# yarns_v03.net
KiCad netlist of a schematic drawn in EAGLE
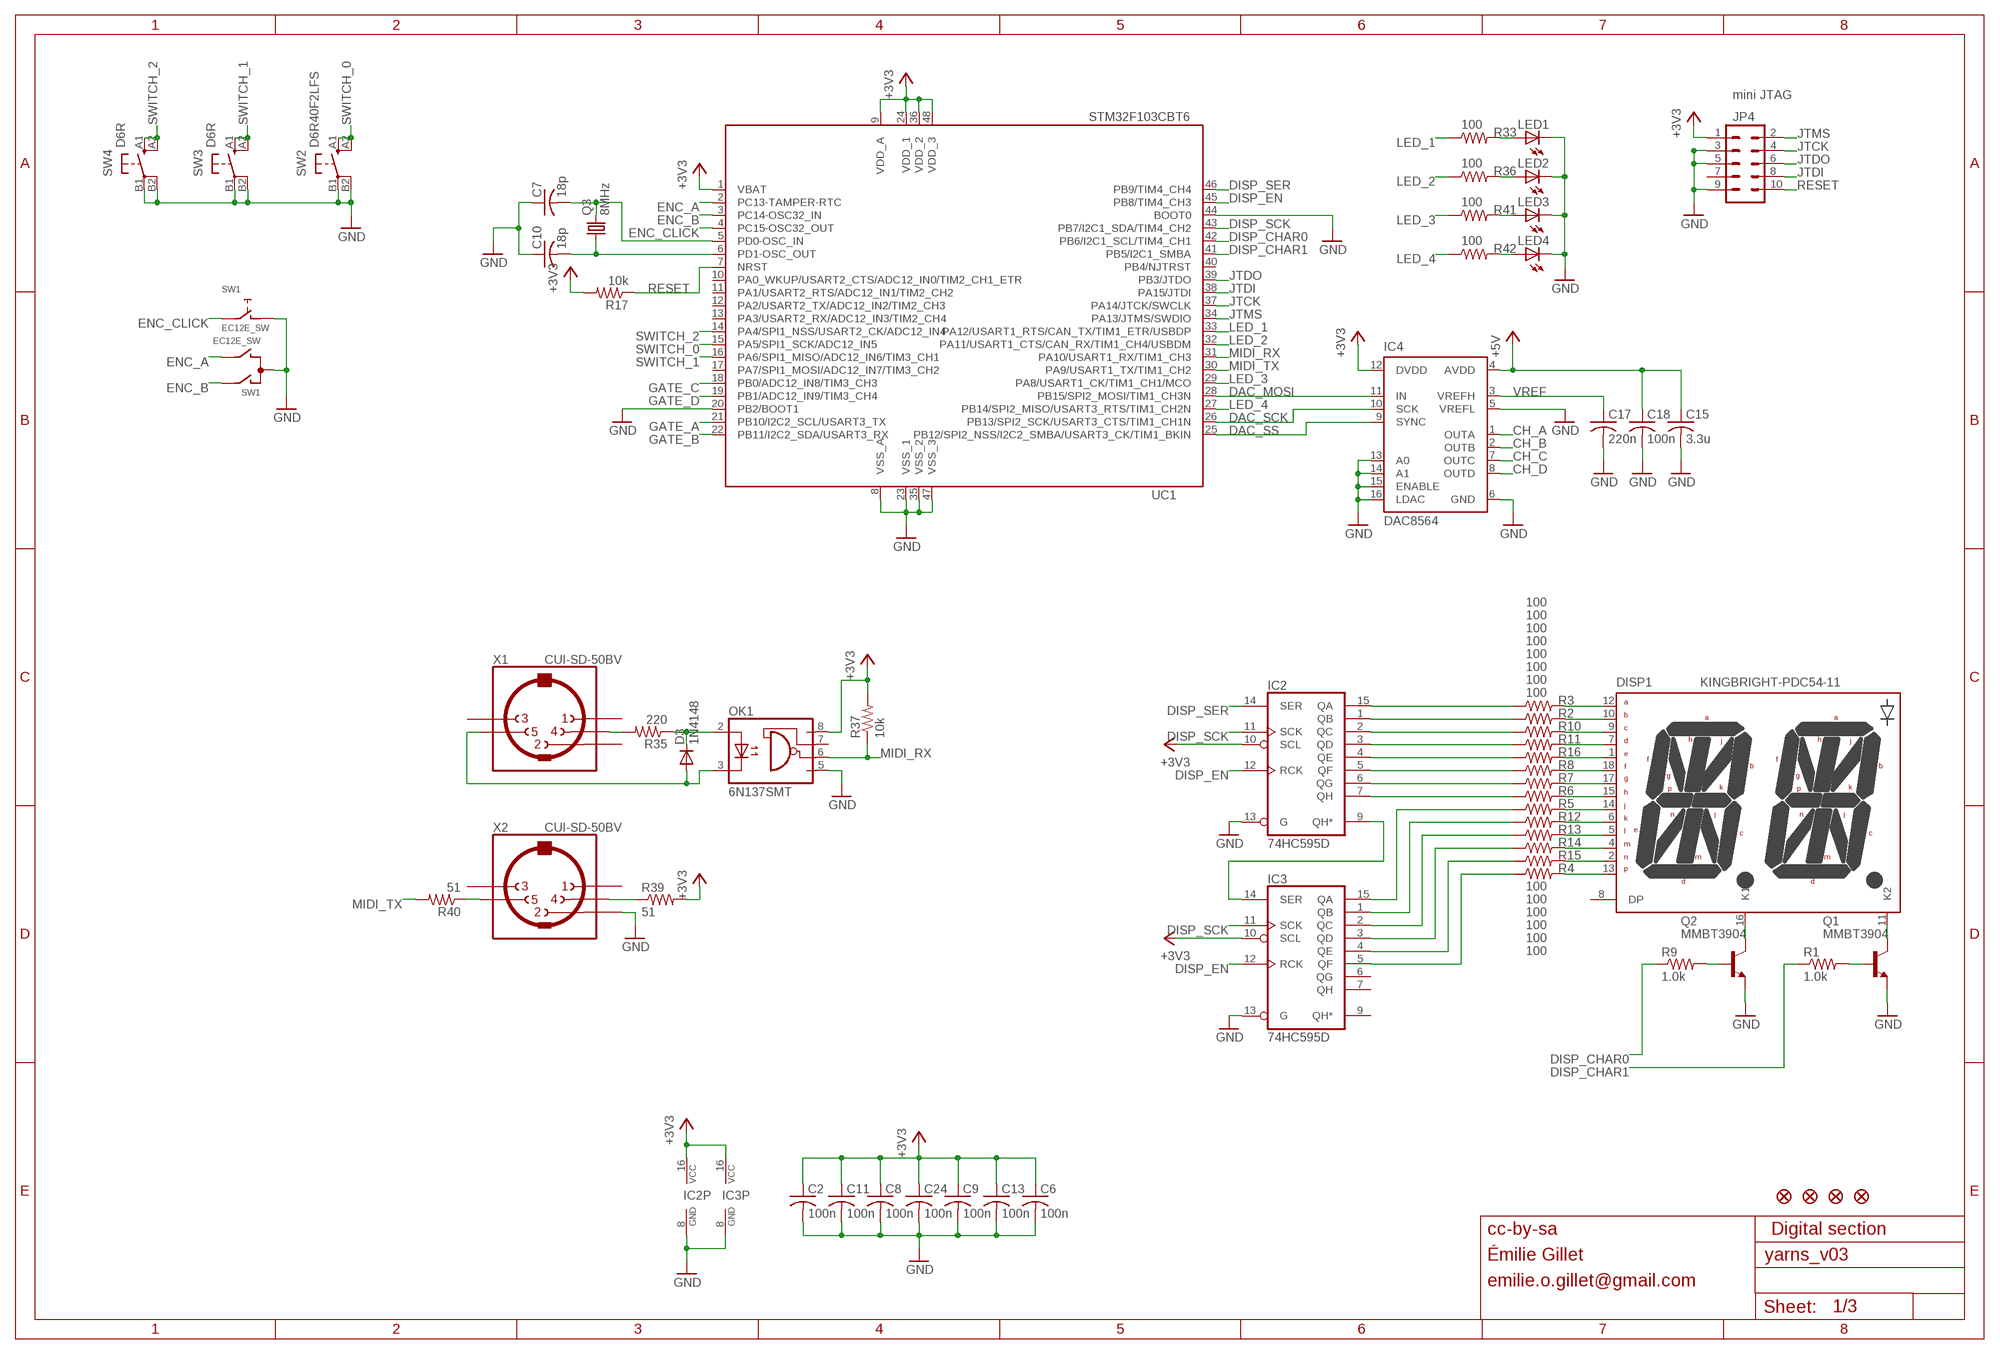
[diagram p0: schematic, sheet 1]
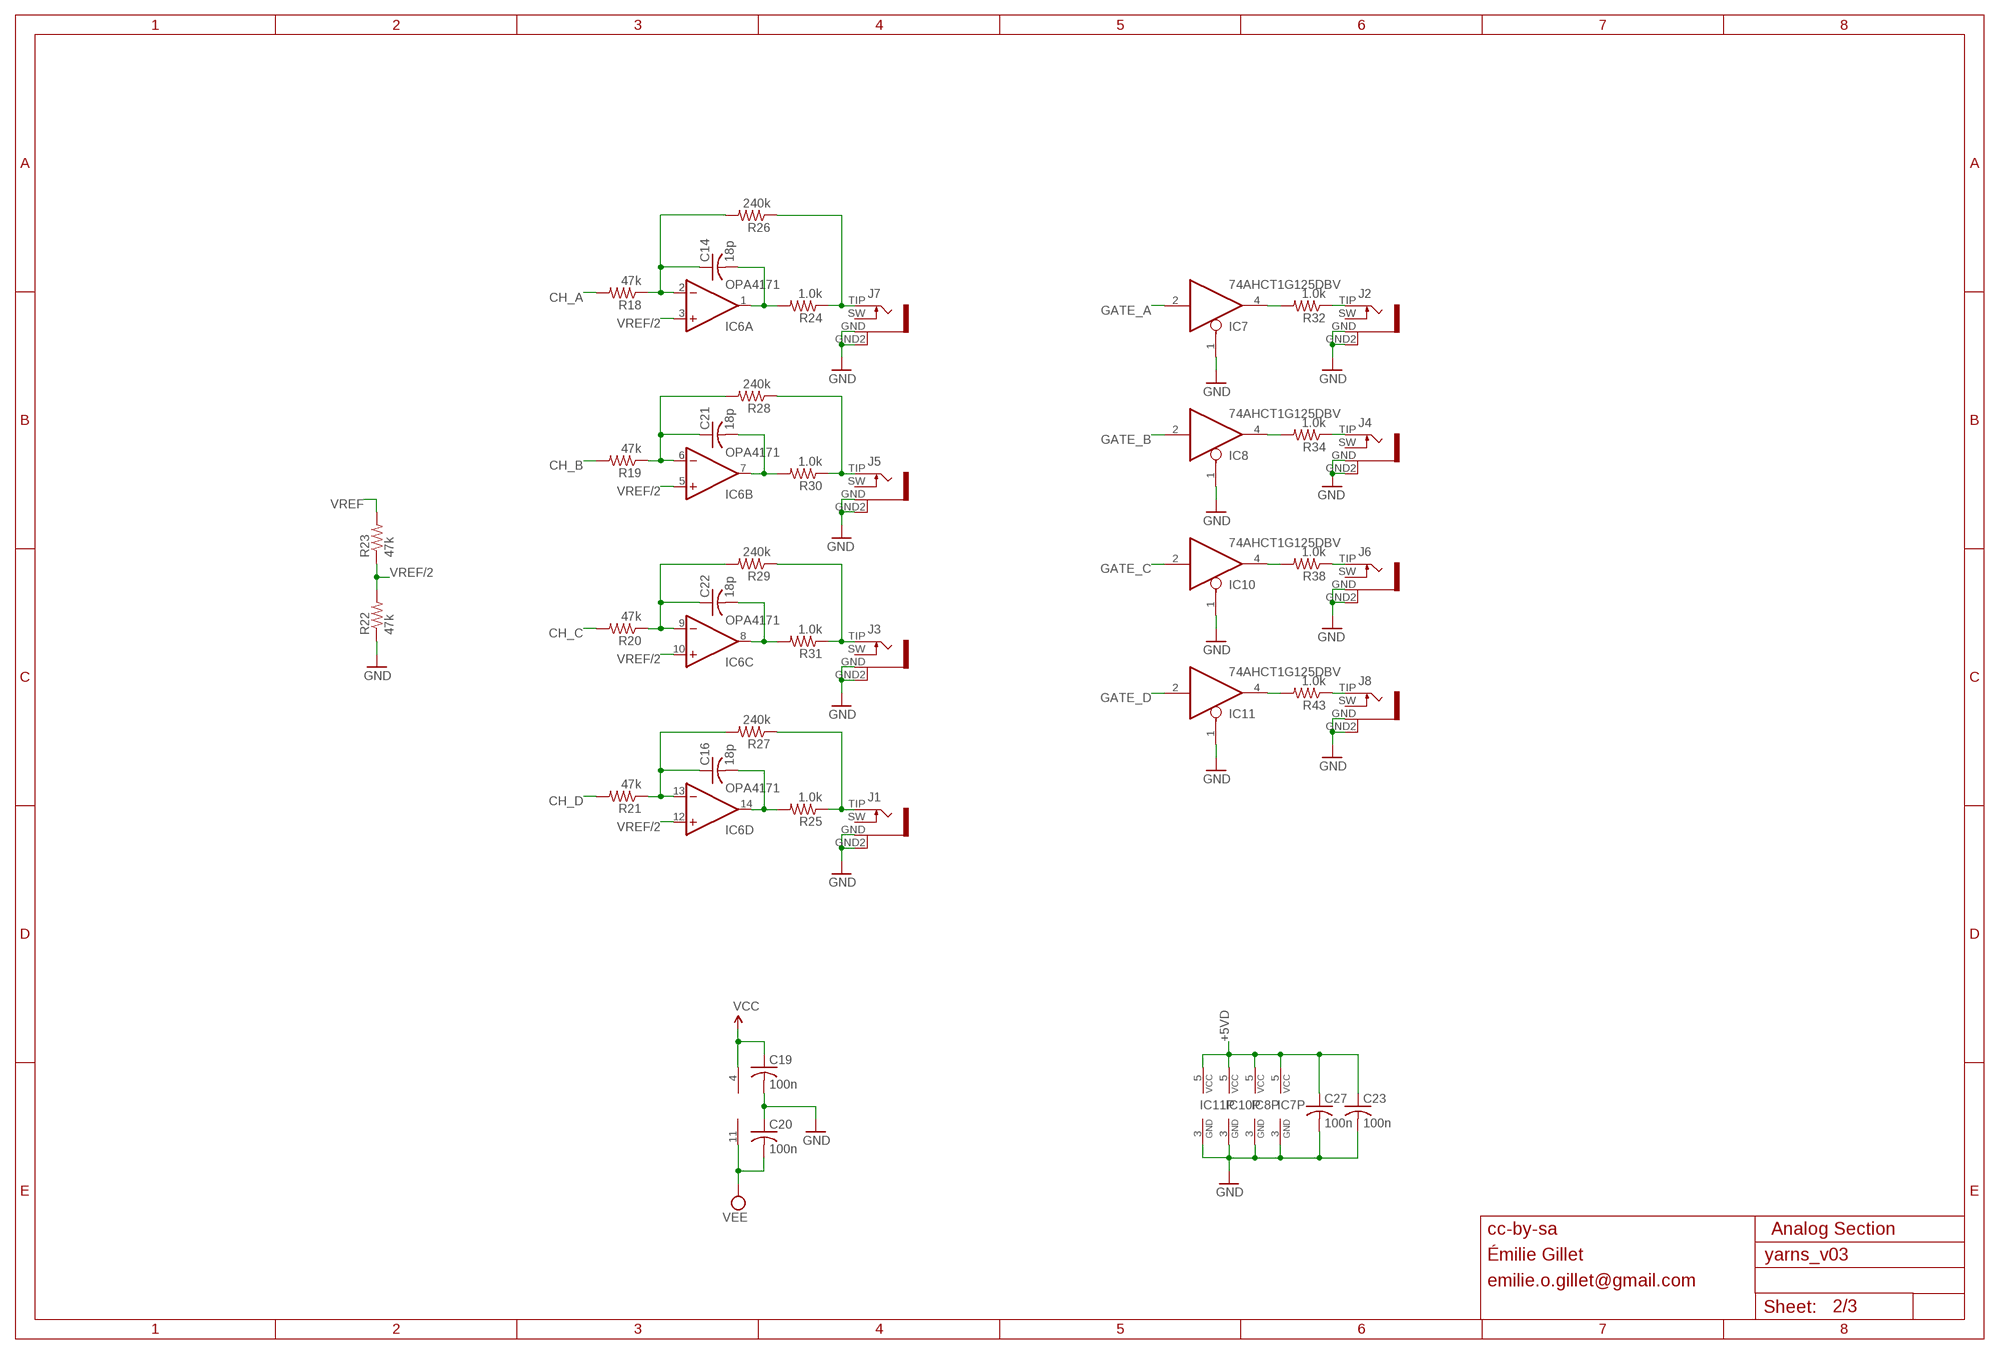
[diagram p1: schematic, sheet 2]
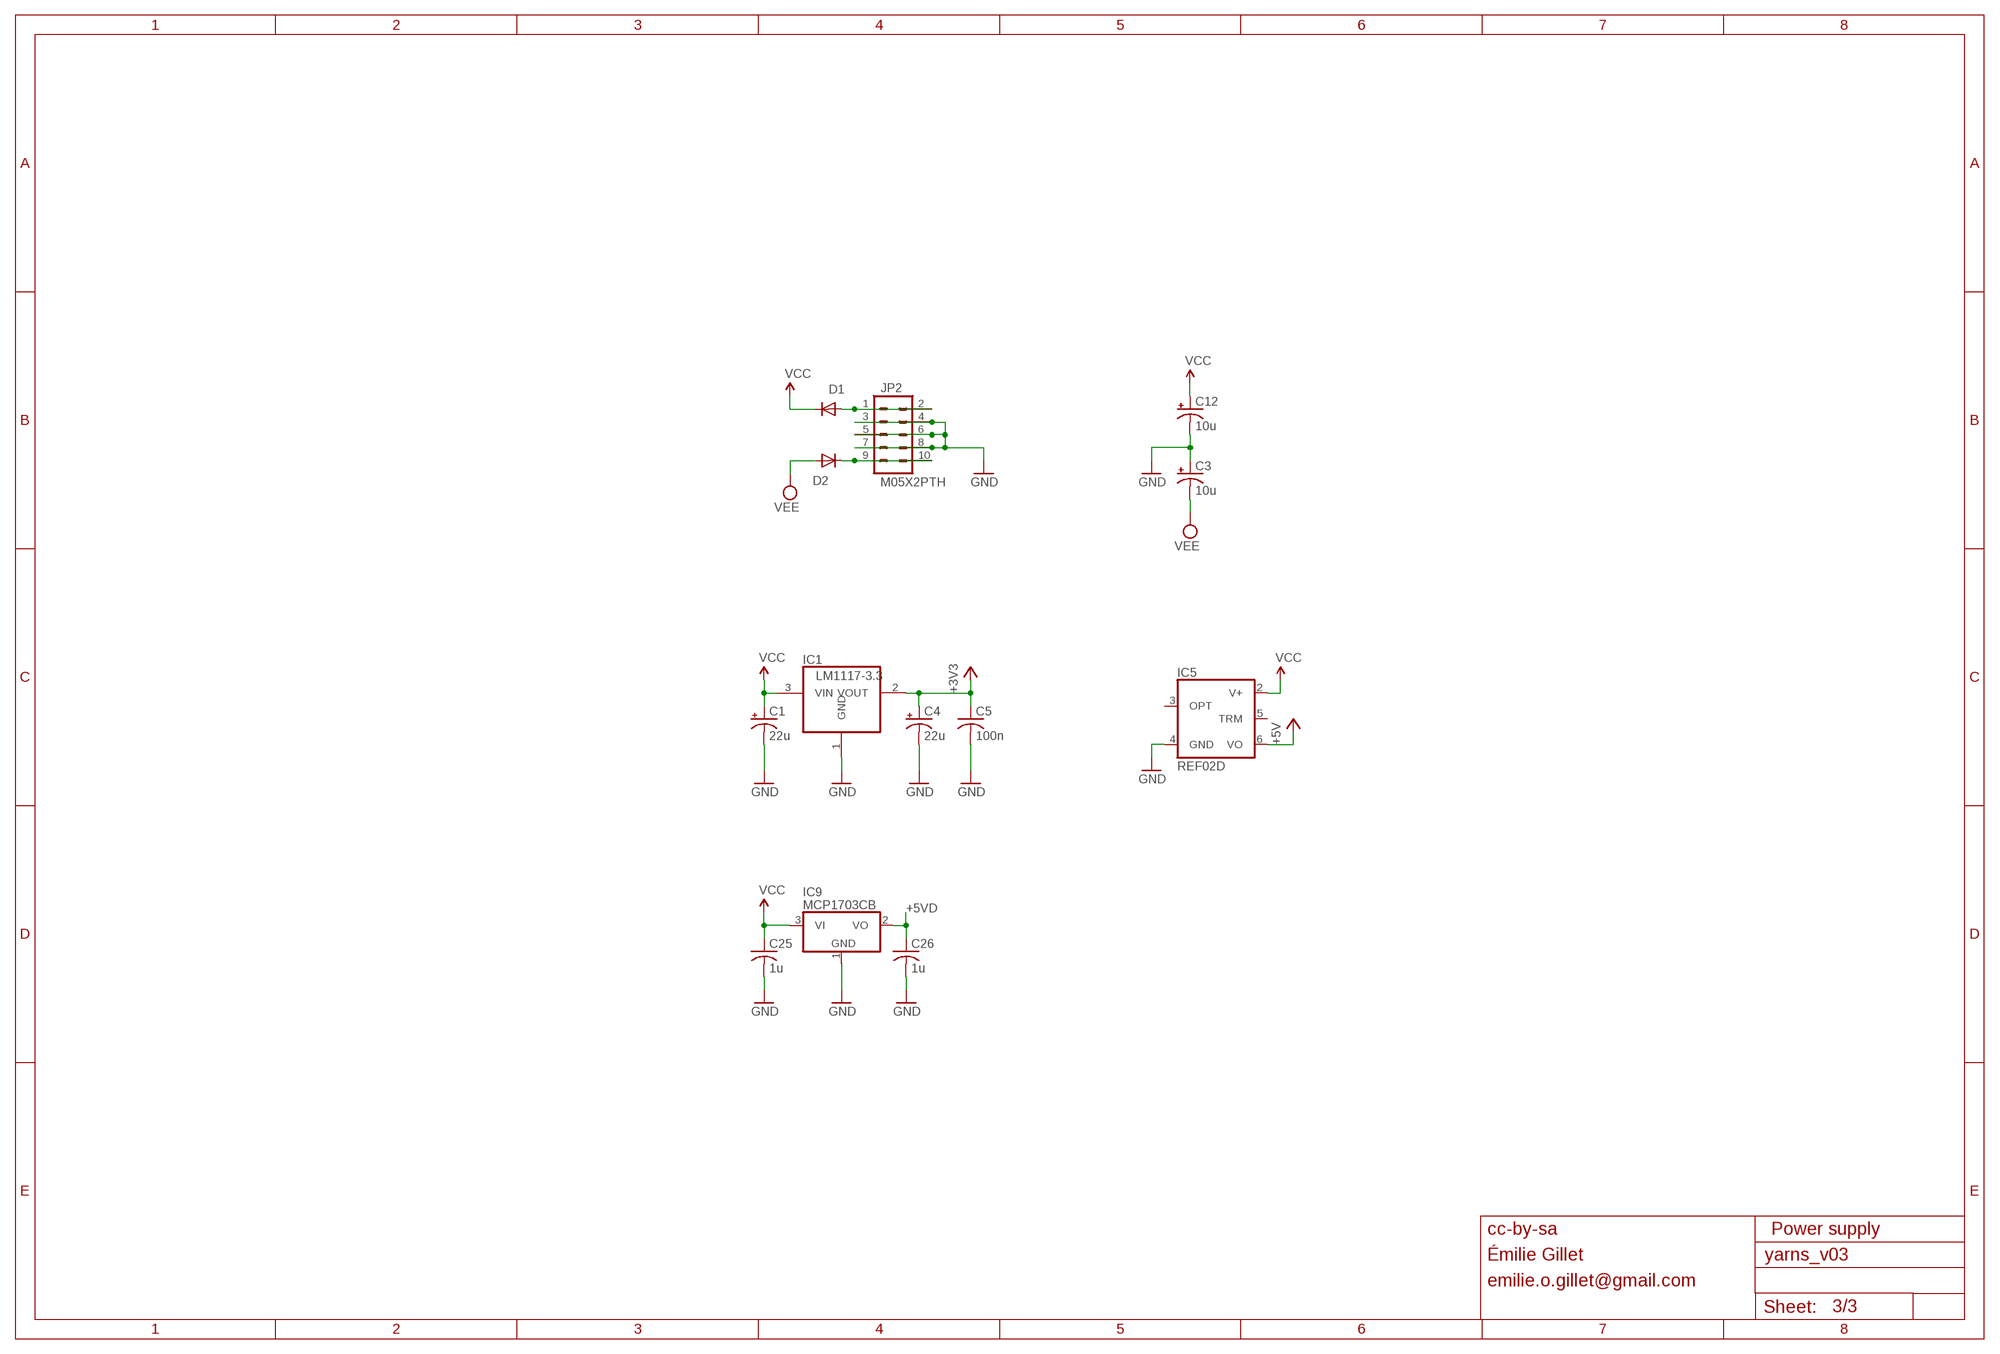
[diagram p2: schematic, sheet 3]

(export (version "E")
  (design (tool "Eeschema 10.0.6"))
  (components
    (comp (ref "C2")
      (value "100n")
      (footprint "eagle-import:C0603")
      (libsource (lib "eagle-import") (part "C-USC0603"))
    )
    (comp (ref "C6")
      (value "100n")
      (footprint "eagle-import:C0603")
      (libsource (lib "eagle-import") (part "C-USC0603"))
    )
    (comp (ref "C7")
      (value "18p")
      (footprint "eagle-import:C0603")
      (libsource (lib "eagle-import") (part "C-USC0603"))
    )
    (comp (ref "C8")
      (value "100n")
      (footprint "eagle-import:C0603")
      (libsource (lib "eagle-import") (part "C-USC0603"))
    )
    (comp (ref "C9")
      (value "100n")
      (footprint "eagle-import:C0603")
      (libsource (lib "eagle-import") (part "C-USC0603"))
    )
    (comp (ref "C10")
      (value "18p")
      (footprint "eagle-import:C0603")
      (libsource (lib "eagle-import") (part "C-USC0603"))
    )
    (comp (ref "C11")
      (value "100n")
      (footprint "eagle-import:C0603")
      (libsource (lib "eagle-import") (part "C-USC0603"))
    )
    (comp (ref "C13")
      (value "100n")
      (footprint "eagle-import:C0603")
      (libsource (lib "eagle-import") (part "C-USC0603"))
    )
    (comp (ref "C15")
      (value "3.3u")
      (footprint "eagle-import:C0603")
      (libsource (lib "eagle-import") (part "C-USC0603"))
    )
    (comp (ref "C17")
      (value "220n")
      (footprint "eagle-import:C0603")
      (libsource (lib "eagle-import") (part "C-USC0603"))
    )
    (comp (ref "C18")
      (value "100n")
      (footprint "eagle-import:C0603")
      (libsource (lib "eagle-import") (part "C-USC0603"))
    )
    (comp (ref "C24")
      (value "100n")
      (footprint "eagle-import:C0603")
      (libsource (lib "eagle-import") (part "C-USC0603"))
    )
    (comp (ref "D3")
      (value "1N4148")
      (footprint "eagle-import:SOD323-W")
      (libsource (lib "eagle-import") (part "DIODE-SOD323-W"))
    )
    (comp (ref "DISP1")
      (value "KINGBRIGHT-PDC54-11")
      (footprint "eagle-import:PDC54")
      (libsource (lib "eagle-import") (part "KINGBRIGHT-PDC54-11"))
    )
    (comp (ref "F1")
      (value "FIDUCIAL1X2")
      (footprint "eagle-import:FIDUCIAL-1X2")
      (libsource (lib "eagle-import") (part "FIDUCIAL1X2"))
    )
    (comp (ref "F3")
      (value "FIDUCIAL1X2")
      (footprint "eagle-import:FIDUCIAL-1X2")
      (libsource (lib "eagle-import") (part "FIDUCIAL1X2"))
    )
    (comp (ref "F5")
      (value "FIDUCIAL1X2")
      (footprint "eagle-import:FIDUCIAL-1X2")
      (libsource (lib "eagle-import") (part "FIDUCIAL1X2"))
    )
    (comp (ref "F6")
      (value "FIDUCIAL1X2")
      (footprint "eagle-import:FIDUCIAL-1X2")
      (libsource (lib "eagle-import") (part "FIDUCIAL1X2"))
    )
    (comp (ref "IC2")
      (value "74HC595D")
      (footprint "eagle-import:SO16")
      (libsource (lib "eagle-import") (part "74595DHC"))
    )
    (comp (ref "IC3")
      (value "74HC595D")
      (footprint "eagle-import:SO16")
      (libsource (lib "eagle-import") (part "74595DHC"))
    )
    (comp (ref "IC4")
      (value "DAC8564")
      (footprint "eagle-import:SOP65P640X110-16N")
      (libsource (lib "eagle-import") (part "DAC8564"))
    )
    (comp (ref "JP4")
      (value "M05X2MINIJTAG")
      (footprint "eagle-import:2X5-1.27")
      (libsource (lib "eagle-import") (part "M05X2MINIJTAG"))
    )
    (comp (ref "LED1")
      (value "LED3MM")
      (footprint "eagle-import:LED3MM")
      (libsource (lib "eagle-import") (part "LED3MM"))
    )
    (comp (ref "LED2")
      (value "LED3MM")
      (footprint "eagle-import:LED3MM")
      (libsource (lib "eagle-import") (part "LED3MM"))
    )
    (comp (ref "LED3")
      (value "LED3MM")
      (footprint "eagle-import:LED3MM")
      (libsource (lib "eagle-import") (part "LED3MM"))
    )
    (comp (ref "LED4")
      (value "LED3MM")
      (footprint "eagle-import:LED3MM")
      (libsource (lib "eagle-import") (part "LED3MM"))
    )
    (comp (ref "OK1")
      (value "6N137SMT")
      (footprint "eagle-import:DIL8-SMD")
      (libsource (lib "eagle-import") (part "6N137SMT"))
    )
    (comp (ref "Q1")
      (value "MMBT3904")
      (footprint "eagle-import:SOT23-BEC")
      (libsource (lib "eagle-import") (part "-NPN-SOT23-BECMMBT3904LT1"))
    )
    (comp (ref "Q2")
      (value "MMBT3904")
      (footprint "eagle-import:SOT23-BEC")
      (libsource (lib "eagle-import") (part "-NPN-SOT23-BECMMBT3904LT1"))
    )
    (comp (ref "Q3")
      (value "8MHz")
      (footprint "eagle-import:HC49UP")
      (libsource (lib "eagle-import") (part "CRYSTALHC49UP"))
    )
    (comp (ref "R1")
      (value "1.0k")
      (footprint "eagle-import:R0603")
      (libsource (lib "eagle-import") (part "R-US_R0603"))
    )
    (comp (ref "R2")
      (value "100")
      (footprint "eagle-import:R0603")
      (libsource (lib "eagle-import") (part "R-US_R0603"))
    )
    (comp (ref "R3")
      (value "100")
      (footprint "eagle-import:R0603")
      (libsource (lib "eagle-import") (part "R-US_R0603"))
    )
    (comp (ref "R4")
      (value "100")
      (footprint "eagle-import:R0603")
      (libsource (lib "eagle-import") (part "R-US_R0603"))
    )
    (comp (ref "R5")
      (value "100")
      (footprint "eagle-import:R0603")
      (libsource (lib "eagle-import") (part "R-US_R0603"))
    )
    (comp (ref "R6")
      (value "100")
      (footprint "eagle-import:R0603")
      (libsource (lib "eagle-import") (part "R-US_R0603"))
    )
    (comp (ref "R7")
      (value "100")
      (footprint "eagle-import:R0603")
      (libsource (lib "eagle-import") (part "R-US_R0603"))
    )
    (comp (ref "R8")
      (value "100")
      (footprint "eagle-import:R0603")
      (libsource (lib "eagle-import") (part "R-US_R0603"))
    )
    (comp (ref "R9")
      (value "1.0k")
      (footprint "eagle-import:R0603")
      (libsource (lib "eagle-import") (part "R-US_R0603"))
    )
    (comp (ref "R10")
      (value "100")
      (footprint "eagle-import:R0603")
      (libsource (lib "eagle-import") (part "R-US_R0603"))
    )
    (comp (ref "R11")
      (value "100")
      (footprint "eagle-import:R0603")
      (libsource (lib "eagle-import") (part "R-US_R0603"))
    )
    (comp (ref "R12")
      (value "100")
      (footprint "eagle-import:R0603")
      (libsource (lib "eagle-import") (part "R-US_R0603"))
    )
    (comp (ref "R13")
      (value "100")
      (footprint "eagle-import:R0603")
      (libsource (lib "eagle-import") (part "R-US_R0603"))
    )
    (comp (ref "R14")
      (value "100")
      (footprint "eagle-import:R0603")
      (libsource (lib "eagle-import") (part "R-US_R0603"))
    )
    (comp (ref "R15")
      (value "100")
      (footprint "eagle-import:R0603")
      (libsource (lib "eagle-import") (part "R-US_R0603"))
    )
    (comp (ref "R16")
      (value "100")
      (footprint "eagle-import:R0603")
      (libsource (lib "eagle-import") (part "R-US_R0603"))
    )
    (comp (ref "R17")
      (value "10k")
      (footprint "eagle-import:R0603")
      (libsource (lib "eagle-import") (part "R-US_R0603"))
    )
    (comp (ref "R33")
      (value "100")
      (footprint "eagle-import:R0603")
      (libsource (lib "eagle-import") (part "R-US_R0603"))
    )
    (comp (ref "R35")
      (value "220")
      (footprint "eagle-import:R0603")
      (libsource (lib "eagle-import") (part "R-US_R0603"))
    )
    (comp (ref "R36")
      (value "100")
      (footprint "eagle-import:R0603")
      (libsource (lib "eagle-import") (part "R-US_R0603"))
    )
    (comp (ref "R37")
      (value "10k")
      (footprint "eagle-import:R0603")
      (libsource (lib "eagle-import") (part "R-US_R0603"))
    )
    (comp (ref "R39")
      (value "51")
      (footprint "eagle-import:R0603")
      (libsource (lib "eagle-import") (part "R-US_R0603"))
    )
    (comp (ref "R40")
      (value "51")
      (footprint "eagle-import:R0603")
      (libsource (lib "eagle-import") (part "R-US_R0603"))
    )
    (comp (ref "R41")
      (value "100")
      (footprint "eagle-import:R0603")
      (libsource (lib "eagle-import") (part "R-US_R0603"))
    )
    (comp (ref "R42")
      (value "100")
      (footprint "eagle-import:R0603")
      (libsource (lib "eagle-import") (part "R-US_R0603"))
    )
    (comp (ref "SW1")
      (value "EC12E_SW")
      (footprint "eagle-import:ALPS_EC12E_SW")
      (libsource (lib "eagle-import") (part "EC12E_SW"))
    )
    (comp (ref "SW2")
      (value "D6R40F2LFS")
      (footprint "eagle-import:D6R")
      (libsource (lib "eagle-import") (part "D6R"))
    )
    (comp (ref "SW3")
      (value "D6R")
      (footprint "eagle-import:D6R")
      (libsource (lib "eagle-import") (part "D6R"))
    )
    (comp (ref "SW4")
      (value "D6R")
      (footprint "eagle-import:D6R")
      (libsource (lib "eagle-import") (part "D6R"))
    )
    (comp (ref "UC1")
      (value "STM32F103CBT6")
      (footprint "eagle-import:LQFP48")
      (libsource (lib "eagle-import") (part "STM32F103CB"))
    )
    (comp (ref "X1")
      (value "CUI-SD-50BV")
      (footprint "eagle-import:SD-50BV")
      (libsource (lib "eagle-import") (part "MAB5SHCUI-SD-50BV"))
    )
    (comp (ref "X2")
      (value "CUI-SD-50BV")
      (footprint "eagle-import:SD-50BV")
      (libsource (lib "eagle-import") (part "MAB5SHCUI-SD-50BV"))
    )
    (comp (ref "C14")
      (value "18p")
      (footprint "eagle-import:C0603")
      (libsource (lib "eagle-import") (part "C-USC0603"))
    )
    (comp (ref "C16")
      (value "18p")
      (footprint "eagle-import:C0603")
      (libsource (lib "eagle-import") (part "C-USC0603"))
    )
    (comp (ref "C19")
      (value "100n")
      (footprint "eagle-import:C0603")
      (libsource (lib "eagle-import") (part "C-USC0603"))
    )
    (comp (ref "C20")
      (value "100n")
      (footprint "eagle-import:C0603")
      (libsource (lib "eagle-import") (part "C-USC0603"))
    )
    (comp (ref "C21")
      (value "18p")
      (footprint "eagle-import:C0603")
      (libsource (lib "eagle-import") (part "C-USC0603"))
    )
    (comp (ref "C22")
      (value "18p")
      (footprint "eagle-import:C0603")
      (libsource (lib "eagle-import") (part "C-USC0603"))
    )
    (comp (ref "C23")
      (value "100n")
      (footprint "eagle-import:C0603")
      (libsource (lib "eagle-import") (part "C-USC0603"))
    )
    (comp (ref "C27")
      (value "100n")
      (footprint "eagle-import:C0603")
      (libsource (lib "eagle-import") (part "C-USC0603"))
    )
    (comp (ref "IC6")
      (value "OPA4171")
      (footprint "eagle-import:SO14")
      (libsource (lib "eagle-import") (part "TL074D"))
    )
    (comp (ref "IC7")
      (value "74AHCT1G125DBV")
      (footprint "eagle-import:SOT23-5")
      (libsource (lib "eagle-import") (part "741G125DBVAHCT"))
    )
    (comp (ref "IC8")
      (value "74AHCT1G125DBV")
      (footprint "eagle-import:SOT23-5")
      (libsource (lib "eagle-import") (part "741G125DBVAHCT"))
    )
    (comp (ref "IC10")
      (value "74AHCT1G125DBV")
      (footprint "eagle-import:SOT23-5")
      (libsource (lib "eagle-import") (part "741G125DBVAHCT"))
    )
    (comp (ref "IC11")
      (value "74AHCT1G125DBV")
      (footprint "eagle-import:SOT23-5")
      (libsource (lib "eagle-import") (part "741G125DBVAHCT"))
    )
    (comp (ref "J1")
      (value "PJ301WQP")
      (footprint "eagle-import:WQP_PJ_301BM")
      (libsource (lib "eagle-import") (part "PJ301WQP"))
    )
    (comp (ref "J2")
      (value "PJ301WQP")
      (footprint "eagle-import:WQP_PJ_301BM")
      (libsource (lib "eagle-import") (part "PJ301WQP"))
    )
    (comp (ref "J3")
      (value "PJ301WQP")
      (footprint "eagle-import:WQP_PJ_301BM")
      (libsource (lib "eagle-import") (part "PJ301WQP"))
    )
    (comp (ref "J4")
      (value "PJ301WQP")
      (footprint "eagle-import:WQP_PJ_301BM")
      (libsource (lib "eagle-import") (part "PJ301WQP"))
    )
    (comp (ref "J5")
      (value "PJ301WQP")
      (footprint "eagle-import:WQP_PJ_301BM")
      (libsource (lib "eagle-import") (part "PJ301WQP"))
    )
    (comp (ref "J6")
      (value "PJ301WQP")
      (footprint "eagle-import:WQP_PJ_301BM")
      (libsource (lib "eagle-import") (part "PJ301WQP"))
    )
    (comp (ref "J7")
      (value "PJ301WQP")
      (footprint "eagle-import:WQP_PJ_301BM")
      (libsource (lib "eagle-import") (part "PJ301WQP"))
    )
    (comp (ref "J8")
      (value "PJ301WQP")
      (footprint "eagle-import:WQP_PJ_301BM")
      (libsource (lib "eagle-import") (part "PJ301WQP"))
    )
    (comp (ref "R18")
      (value "47k")
      (footprint "eagle-import:R0603")
      (libsource (lib "eagle-import") (part "R-US_R0603"))
    )
    (comp (ref "R19")
      (value "47k")
      (footprint "eagle-import:R0603")
      (libsource (lib "eagle-import") (part "R-US_R0603"))
    )
    (comp (ref "R20")
      (value "47k")
      (footprint "eagle-import:R0603")
      (libsource (lib "eagle-import") (part "R-US_R0603"))
    )
    (comp (ref "R21")
      (value "47k")
      (footprint "eagle-import:R0603")
      (libsource (lib "eagle-import") (part "R-US_R0603"))
    )
    (comp (ref "R22")
      (value "47k")
      (footprint "eagle-import:R0603")
      (libsource (lib "eagle-import") (part "R-US_R0603"))
    )
    (comp (ref "R23")
      (value "47k")
      (footprint "eagle-import:R0603")
      (libsource (lib "eagle-import") (part "R-US_R0603"))
    )
    (comp (ref "R24")
      (value "1.0k")
      (footprint "eagle-import:R0603")
      (libsource (lib "eagle-import") (part "R-US_R0603"))
    )
    (comp (ref "R25")
      (value "1.0k")
      (footprint "eagle-import:R0603")
      (libsource (lib "eagle-import") (part "R-US_R0603"))
    )
    (comp (ref "R26")
      (value "240k")
      (footprint "eagle-import:R0603")
      (libsource (lib "eagle-import") (part "R-US_R0603"))
    )
    (comp (ref "R27")
      (value "240k")
      (footprint "eagle-import:R0603")
      (libsource (lib "eagle-import") (part "R-US_R0603"))
    )
    (comp (ref "R28")
      (value "240k")
      (footprint "eagle-import:R0603")
      (libsource (lib "eagle-import") (part "R-US_R0603"))
    )
    (comp (ref "R29")
      (value "240k")
      (footprint "eagle-import:R0603")
      (libsource (lib "eagle-import") (part "R-US_R0603"))
    )
    (comp (ref "R30")
      (value "1.0k")
      (footprint "eagle-import:R0603")
      (libsource (lib "eagle-import") (part "R-US_R0603"))
    )
    (comp (ref "R31")
      (value "1.0k")
      (footprint "eagle-import:R0603")
      (libsource (lib "eagle-import") (part "R-US_R0603"))
    )
    (comp (ref "R32")
      (value "1.0k")
      (footprint "eagle-import:R0603")
      (libsource (lib "eagle-import") (part "R-US_R0603"))
    )
    (comp (ref "R34")
      (value "1.0k")
      (footprint "eagle-import:R0603")
      (libsource (lib "eagle-import") (part "R-US_R0603"))
    )
    (comp (ref "R38")
      (value "1.0k")
      (footprint "eagle-import:R0603")
      (libsource (lib "eagle-import") (part "R-US_R0603"))
    )
    (comp (ref "R43")
      (value "1.0k")
      (footprint "eagle-import:R0603")
      (libsource (lib "eagle-import") (part "R-US_R0603"))
    )
    (comp (ref "C1")
      (value "22u")
      (footprint "eagle-import:PANASONIC_C")
      (libsource (lib "eagle-import") (part "CPOL-USC"))
    )
    (comp (ref "C3")
      (value "10u")
      (footprint "eagle-import:PANASONIC_A")
      (libsource (lib "eagle-import") (part "CPOL-USA"))
    )
    (comp (ref "C4")
      (value "22u")
      (footprint "eagle-import:PANASONIC_C")
      (libsource (lib "eagle-import") (part "CPOL-USC"))
    )
    (comp (ref "C5")
      (value "100n")
      (footprint "eagle-import:C0603")
      (libsource (lib "eagle-import") (part "C-USC0603"))
    )
    (comp (ref "C12")
      (value "10u")
      (footprint "eagle-import:PANASONIC_A")
      (libsource (lib "eagle-import") (part "CPOL-USA"))
    )
    (comp (ref "C25")
      (value "1u")
      (footprint "eagle-import:C0603")
      (libsource (lib "eagle-import") (part "C-USC0603"))
    )
    (comp (ref "C26")
      (value "1u")
      (footprint "eagle-import:C0603")
      (libsource (lib "eagle-import") (part "C-USC0603"))
    )
    (comp (ref "D1")
      (value "1N5819HW")
      (footprint "eagle-import:SOD123")
      (libsource (lib "eagle-import") (part "DIODE-SOD123"))
    )
    (comp (ref "D2")
      (value "1N5819HW")
      (footprint "eagle-import:SOD123")
      (libsource (lib "eagle-import") (part "DIODE-SOD123"))
    )
    (comp (ref "IC1")
      (value "LM1117-3.3")
      (footprint "eagle-import:SOT223")
      (libsource (lib "eagle-import") (part "REG1117"))
    )
    (comp (ref "IC5")
      (value "REF02D")
      (footprint "eagle-import:SO08")
      (libsource (lib "eagle-import") (part "REF02D"))
    )
    (comp (ref "IC9")
      (value "MCP1703CB")
      (footprint "eagle-import:SOT23")
      (libsource (lib "eagle-import") (part "MCP1703CB"))
    )
    (comp (ref "JP2")
      (value "M05X2PTH")
      (footprint "eagle-import:AVR_ICSP")
      (libsource (lib "eagle-import") (part "M05X2PTH"))
    )
  )
  (nets
    (net (code "1") (name "+3V3") (class "Default")
      (node (ref "C11") (pin "1") (pinfunction "1_1") (pintype "passive"))
      (node (ref "C13") (pin "1") (pinfunction "1_1") (pintype "passive"))
      (node (ref "C2") (pin "1") (pinfunction "1_1") (pintype "passive"))
      (node (ref "C24") (pin "1") (pinfunction "1_1") (pintype "passive"))
      (node (ref "C4") (pin "+") (pinfunction "+_+") (pintype "passive"))
      (node (ref "C5") (pin "1") (pinfunction "1_1") (pintype "passive"))
      (node (ref "C6") (pin "1") (pinfunction "1_1") (pintype "passive"))
      (node (ref "C8") (pin "1") (pinfunction "1_1") (pintype "passive"))
      (node (ref "C9") (pin "1") (pinfunction "1_1") (pintype "passive"))
      (node (ref "IC1") (pin "2") (pinfunction "VOUT_2") (pintype "output"))
      (node (ref "IC2") (pin "10") (pinfunction "SCL_10") (pintype "input"))
      (node (ref "IC2") (pin "16") (pinfunction "VCC_16") (pintype "power_in"))
      (node (ref "IC3") (pin "10") (pinfunction "SCL_10") (pintype "input"))
      (node (ref "IC3") (pin "16") (pinfunction "VCC_16") (pintype "power_in"))
      (node (ref "IC4") (pin "12") (pinfunction "DVDD_12") (pintype "power_in"))
      (node (ref "JP4") (pin "1") (pinfunction "1_1") (pintype "passive"))
      (node (ref "OK1") (pin "8") (pinfunction "VCC_8") (pintype "passive"))
      (node (ref "R17") (pin "2") (pinfunction "2_2") (pintype "passive"))
      (node (ref "R37") (pin "2") (pinfunction "2_2") (pintype "passive"))
      (node (ref "R39") (pin "2") (pinfunction "2_2") (pintype "passive"))
      (node (ref "UC1") (pin "1") (pinfunction "VBAT_1") (pintype "power_in"))
      (node (ref "UC1") (pin "24") (pinfunction "VDD_1_24") (pintype "power_in"))
      (node (ref "UC1") (pin "36") (pinfunction "VDD_2_36") (pintype "power_in"))
      (node (ref "UC1") (pin "48") (pinfunction "VDD_3_48") (pintype "power_in"))
      (node (ref "UC1") (pin "9") (pinfunction "VDD_A_9") (pintype "power_in"))
    )
    (net (code "2") (name "+5V") (class "Default")
      (node (ref "C15") (pin "1") (pinfunction "1_1") (pintype "passive"))
      (node (ref "C18") (pin "1") (pinfunction "1_1") (pintype "passive"))
      (node (ref "IC4") (pin "4") (pinfunction "AVDD_4") (pintype "power_in"))
      (node (ref "IC5") (pin "6") (pinfunction "VO_6") (pintype "output"))
    )
    (net (code "3") (name "+5VD") (class "Default")
      (node (ref "C23") (pin "1") (pinfunction "1_1") (pintype "passive"))
      (node (ref "C26") (pin "1") (pinfunction "1_1") (pintype "passive"))
      (node (ref "C27") (pin "1") (pinfunction "1_1") (pintype "passive"))
      (node (ref "IC10") (pin "5") (pinfunction "VCC_5") (pintype "power_in"))
      (node (ref "IC11") (pin "5") (pinfunction "VCC_5") (pintype "power_in"))
      (node (ref "IC7") (pin "5") (pinfunction "VCC_5") (pintype "power_in"))
      (node (ref "IC8") (pin "5") (pinfunction "VCC_5") (pintype "power_in"))
      (node (ref "IC9") (pin "2") (pinfunction "VO_2") (pintype "passive"))
    )
    (net (code "4") (name "CH_A") (class "Default")
      (node (ref "IC4") (pin "1") (pinfunction "OUTA_1") (pintype "output"))
      (node (ref "R18") (pin "2") (pinfunction "2_2") (pintype "passive"))
    )
    (net (code "5") (name "CH_B") (class "Default")
      (node (ref "IC4") (pin "2") (pinfunction "OUTB_2") (pintype "output"))
      (node (ref "R19") (pin "2") (pinfunction "2_2") (pintype "passive"))
    )
    (net (code "6") (name "CH_C") (class "Default")
      (node (ref "IC4") (pin "7") (pinfunction "OUTC_7") (pintype "output"))
      (node (ref "R20") (pin "2") (pinfunction "2_2") (pintype "passive"))
    )
    (net (code "7") (name "CH_D") (class "Default")
      (node (ref "IC4") (pin "8") (pinfunction "OUTD_8") (pintype "output"))
      (node (ref "R21") (pin "2") (pinfunction "2_2") (pintype "passive"))
    )
    (net (code "8") (name "DAC_MOSI") (class "Default")
      (node (ref "IC4") (pin "11") (pinfunction "IN_11") (pintype "input"))
      (node (ref "UC1") (pin "28") (pinfunction "PB15/SPI2_MOSI/TIM1_CH3N_28") (pintype "input"))
    )
    (net (code "9") (name "DAC_SCK") (class "Default")
      (node (ref "IC4") (pin "10") (pinfunction "SCK_10") (pintype "input"))
      (node (ref "UC1") (pin "26") (pinfunction "PB13/SPI2_SCK/USART3_CTS/TIM1_CH1N_26") (pintype "input"))
    )
    (net (code "10") (name "DAC_SS") (class "Default")
      (node (ref "IC4") (pin "9") (pinfunction "SYNC_9") (pintype "input"))
      (node (ref "UC1") (pin "25") (pinfunction "PB12/SPI2_NSS/I2C2_SMBA/USART3_CK/TIM1_BKIN_25") (pintype "input"))
    )
    (net (code "11") (name "DISP_CHAR0") (class "Default")
      (node (ref "R9") (pin "1") (pinfunction "1_1") (pintype "passive"))
      (node (ref "UC1") (pin "42") (pinfunction "PB6/I2C1_SCL/TIM4_CH1_42") (pintype "input"))
    )
    (net (code "12") (name "DISP_CHAR1") (class "Default")
      (node (ref "R1") (pin "1") (pinfunction "1_1") (pintype "passive"))
      (node (ref "UC1") (pin "41") (pinfunction "PB5/I2C1_SMBA_41") (pintype "input"))
    )
    (net (code "13") (name "DISP_EN") (class "Default")
      (node (ref "IC2") (pin "12") (pinfunction "RCK_12") (pintype "input"))
      (node (ref "IC3") (pin "12") (pinfunction "RCK_12") (pintype "input"))
      (node (ref "UC1") (pin "45") (pinfunction "PB8/TIM4_CH3_45") (pintype "bidirectional"))
    )
    (net (code "14") (name "DISP_SCK") (class "Default")
      (node (ref "IC2") (pin "11") (pinfunction "SCK_11") (pintype "input"))
      (node (ref "IC3") (pin "11") (pinfunction "SCK_11") (pintype "input"))
      (node (ref "UC1") (pin "43") (pinfunction "PB7/I2C1_SDA/TIM4_CH2_43") (pintype "bidirectional"))
    )
    (net (code "15") (name "DISP_SER") (class "Default")
      (node (ref "IC2") (pin "14") (pinfunction "SER_14") (pintype "input"))
      (node (ref "UC1") (pin "46") (pinfunction "PB9/TIM4_CH4_46") (pintype "input"))
    )
    (net (code "16") (name "ENC_A") (class "Default")
      (node (ref "SW1") (pin "B") (pinfunction "B_B") (pintype "passive"))
      (node (ref "UC1") (pin "2") (pinfunction "PC13-TAMPER-RTC_2") (pintype "input"))
    )
    (net (code "17") (name "ENC_B") (class "Default")
      (node (ref "SW1") (pin "A") (pinfunction "A_A") (pintype "passive"))
      (node (ref "UC1") (pin "3") (pinfunction "PC14-OSC32_IN_3") (pintype "input"))
    )
    (net (code "18") (name "ENC_CLICK") (class "Default")
      (node (ref "SW1") (pin "E") (pinfunction "2_E") (pintype "passive"))
      (node (ref "UC1") (pin "4") (pinfunction "PC15-OSC32_OUT_4") (pintype "input"))
    )
    (net (code "19") (name "GATE_A") (class "Default")
      (node (ref "IC7") (pin "2") (pinfunction "I_2") (pintype "input"))
      (node (ref "UC1") (pin "21") (pinfunction "PB10/I2C2_SCL/USART3_TX_21") (pintype "input"))
    )
    (net (code "20") (name "GATE_B") (class "Default")
      (node (ref "IC8") (pin "2") (pinfunction "I_2") (pintype "input"))
      (node (ref "UC1") (pin "22") (pinfunction "PB11/I2C2_SDA/USART3_RX_22") (pintype "input"))
    )
    (net (code "21") (name "GATE_C") (class "Default")
      (node (ref "IC10") (pin "2") (pinfunction "I_2") (pintype "input"))
      (node (ref "UC1") (pin "18") (pinfunction "PB0/ADC12_IN8/TIM3_CH3_18") (pintype "bidirectional"))
    )
    (net (code "22") (name "GATE_D") (class "Default")
      (node (ref "IC11") (pin "2") (pinfunction "I_2") (pintype "input"))
      (node (ref "UC1") (pin "19") (pinfunction "PB1/ADC12_IN9/TIM3_CH4_19") (pintype "bidirectional"))
    )
    (net (code "23") (name "GND") (class "Default")
      (node (ref "C1") (pin "-") (pinfunction "-_-") (pintype "passive"))
      (node (ref "C10") (pin "1") (pinfunction "1_1") (pintype "passive"))
      (node (ref "C11") (pin "2") (pinfunction "2_2") (pintype "passive"))
      (node (ref "C12") (pin "-") (pinfunction "-_-") (pintype "passive"))
      (node (ref "C13") (pin "2") (pinfunction "2_2") (pintype "passive"))
      (node (ref "C15") (pin "2") (pinfunction "2_2") (pintype "passive"))
      (node (ref "C17") (pin "2") (pinfunction "2_2") (pintype "passive"))
      (node (ref "C18") (pin "2") (pinfunction "2_2") (pintype "passive"))
      (node (ref "C19") (pin "2") (pinfunction "2_2") (pintype "passive"))
      (node (ref "C2") (pin "2") (pinfunction "2_2") (pintype "passive"))
      (node (ref "C20") (pin "1") (pinfunction "1_1") (pintype "passive"))
      (node (ref "C23") (pin "2") (pinfunction "2_2") (pintype "passive"))
      (node (ref "C24") (pin "2") (pinfunction "2_2") (pintype "passive"))
      (node (ref "C25") (pin "2") (pinfunction "2_2") (pintype "passive"))
      (node (ref "C26") (pin "2") (pinfunction "2_2") (pintype "passive"))
      (node (ref "C27") (pin "2") (pinfunction "2_2") (pintype "passive"))
      (node (ref "C3") (pin "+") (pinfunction "+_+") (pintype "passive"))
      (node (ref "C4") (pin "-") (pinfunction "-_-") (pintype "passive"))
      (node (ref "C5") (pin "2") (pinfunction "2_2") (pintype "passive"))
      (node (ref "C6") (pin "2") (pinfunction "2_2") (pintype "passive"))
      (node (ref "C7") (pin "1") (pinfunction "1_1") (pintype "passive"))
      (node (ref "C8") (pin "2") (pinfunction "2_2") (pintype "passive"))
      (node (ref "C9") (pin "2") (pinfunction "2_2") (pintype "passive"))
      (node (ref "IC1") (pin "1") (pinfunction "GND_1") (pintype "power_in"))
      (node (ref "IC10") (pin "1") (pinfunction "OE_1") (pintype "input"))
      (node (ref "IC10") (pin "3") (pinfunction "GND_3") (pintype "power_in"))
      (node (ref "IC11") (pin "1") (pinfunction "OE_1") (pintype "input"))
      (node (ref "IC11") (pin "3") (pinfunction "GND_3") (pintype "power_in"))
      (node (ref "IC2") (pin "13") (pinfunction "G_13") (pintype "input"))
      (node (ref "IC2") (pin "8") (pinfunction "GND_8") (pintype "power_in"))
      (node (ref "IC3") (pin "13") (pinfunction "G_13") (pintype "input"))
      (node (ref "IC3") (pin "8") (pinfunction "GND_8") (pintype "power_in"))
      (node (ref "IC4") (pin "13") (pinfunction "A0_13") (pintype "input"))
      (node (ref "IC4") (pin "14") (pinfunction "A1_14") (pintype "input"))
      (node (ref "IC4") (pin "15") (pinfunction "ENABLE_15") (pintype "input"))
      (node (ref "IC4") (pin "16") (pinfunction "LDAC_16") (pintype "input"))
      (node (ref "IC4") (pin "5") (pinfunction "VREFL_5") (pintype "bidirectional"))
      (node (ref "IC4") (pin "6") (pinfunction "GND_6") (pintype "power_in"))
      (node (ref "IC5") (pin "4") (pinfunction "GND_4") (pintype "power_in"))
      (node (ref "IC7") (pin "1") (pinfunction "OE_1") (pintype "input"))
      (node (ref "IC7") (pin "3") (pinfunction "GND_3") (pintype "power_in"))
      (node (ref "IC8") (pin "1") (pinfunction "OE_1") (pintype "input"))
      (node (ref "IC8") (pin "3") (pinfunction "GND_3") (pintype "power_in"))
      (node (ref "IC9") (pin "1") (pinfunction "GND_1") (pintype "passive"))
      (node (ref "J1") (pin "GND") (pinfunction "1_GND") (pintype "passive"))
      (node (ref "J1") (pin "GND2") (pinfunction "4_GND2") (pintype "passive"))
      (node (ref "J2") (pin "GND") (pinfunction "1_GND") (pintype "passive"))
      (node (ref "J2") (pin "GND2") (pinfunction "4_GND2") (pintype "passive"))
      (node (ref "J3") (pin "GND") (pinfunction "1_GND") (pintype "passive"))
      (node (ref "J3") (pin "GND2") (pinfunction "4_GND2") (pintype "passive"))
      (node (ref "J4") (pin "GND") (pinfunction "1_GND") (pintype "passive"))
      (node (ref "J4") (pin "GND2") (pinfunction "4_GND2") (pintype "passive"))
      (node (ref "J5") (pin "GND") (pinfunction "1_GND") (pintype "passive"))
      (node (ref "J5") (pin "GND2") (pinfunction "4_GND2") (pintype "passive"))
      (node (ref "J6") (pin "GND") (pinfunction "1_GND") (pintype "passive"))
      (node (ref "J6") (pin "GND2") (pinfunction "4_GND2") (pintype "passive"))
      (node (ref "J7") (pin "GND") (pinfunction "1_GND") (pintype "passive"))
      (node (ref "J7") (pin "GND2") (pinfunction "4_GND2") (pintype "passive"))
      (node (ref "J8") (pin "GND") (pinfunction "1_GND") (pintype "passive"))
      (node (ref "J8") (pin "GND2") (pinfunction "4_GND2") (pintype "passive"))
      (node (ref "JP2") (pin "3") (pinfunction "3_3") (pintype "passive"))
      (node (ref "JP2") (pin "4") (pinfunction "4_4") (pintype "passive"))
      (node (ref "JP2") (pin "5") (pinfunction "5_5") (pintype "passive"))
      (node (ref "JP2") (pin "6") (pinfunction "6_6") (pintype "passive"))
      (node (ref "JP2") (pin "7") (pinfunction "7_7") (pintype "passive"))
      (node (ref "JP2") (pin "8") (pinfunction "8_8") (pintype "passive"))
      (node (ref "JP4") (pin "3") (pinfunction "3_3") (pintype "passive"))
      (node (ref "JP4") (pin "5") (pinfunction "5_5") (pintype "passive"))
      (node (ref "JP4") (pin "9") (pinfunction "9_9") (pintype "passive"))
      (node (ref "LED1") (pin "K") (pinfunction "C_K") (pintype "passive"))
      (node (ref "LED2") (pin "K") (pinfunction "C_K") (pintype "passive"))
      (node (ref "LED3") (pin "K") (pinfunction "C_K") (pintype "passive"))
      (node (ref "LED4") (pin "K") (pinfunction "C_K") (pintype "passive"))
      (node (ref "OK1") (pin "5") (pinfunction "GND_5") (pintype "passive"))
      (node (ref "Q1") (pin "E") (pinfunction "E_E") (pintype "passive"))
      (node (ref "Q2") (pin "E") (pinfunction "E_E") (pintype "passive"))
      (node (ref "R22") (pin "1") (pinfunction "1_1") (pintype "passive"))
      (node (ref "SW1") (pin "C") (pinfunction "C_C") (pintype "passive"))
      (node (ref "SW1") (pin "D") (pinfunction "1_D") (pintype "passive"))
      (node (ref "SW2") (pin "B1") (pinfunction "P_B1") (pintype "passive"))
      (node (ref "SW2") (pin "B2") (pinfunction "P1_B2") (pintype "passive"))
      (node (ref "SW3") (pin "B1") (pinfunction "P_B1") (pintype "passive"))
      (node (ref "SW3") (pin "B2") (pinfunction "P1_B2") (pintype "passive"))
      (node (ref "SW4") (pin "B1") (pinfunction "P_B1") (pintype "passive"))
      (node (ref "SW4") (pin "B2") (pinfunction "P1_B2") (pintype "passive"))
      (node (ref "UC1") (pin "20") (pinfunction "PB2/BOOT1_20") (pintype "bidirectional"))
      (node (ref "UC1") (pin "23") (pinfunction "VSS_1_23") (pintype "power_in"))
      (node (ref "UC1") (pin "35") (pinfunction "VSS_2_35") (pintype "power_in"))
      (node (ref "UC1") (pin "44") (pinfunction "BOOT0_44") (pintype "input"))
      (node (ref "UC1") (pin "47") (pinfunction "VSS_3_47") (pintype "power_in"))
      (node (ref "UC1") (pin "8") (pinfunction "VSS_A_8") (pintype "power_in"))
      (node (ref "X2") (pin "2") (pinfunction "2_2") (pintype "passive"))
    )
    (net (code "24") (name "JTCK") (class "Default")
      (node (ref "JP4") (pin "4") (pinfunction "4_4") (pintype "passive"))
      (node (ref "UC1") (pin "37") (pinfunction "PA14/JTCK/SWCLK_37") (pintype "bidirectional"))
    )
    (net (code "25") (name "JTDI") (class "Default")
      (node (ref "JP4") (pin "8") (pinfunction "8_8") (pintype "passive"))
      (node (ref "UC1") (pin "38") (pinfunction "PA15/JTDI_38") (pintype "bidirectional"))
    )
    (net (code "26") (name "JTDO") (class "Default")
      (node (ref "JP4") (pin "6") (pinfunction "6_6") (pintype "passive"))
      (node (ref "UC1") (pin "39") (pinfunction "PB3/JTDO_39") (pintype "bidirectional"))
    )
    (net (code "27") (name "JTMS") (class "Default")
      (node (ref "JP4") (pin "2") (pinfunction "2_2") (pintype "passive"))
      (node (ref "UC1") (pin "34") (pinfunction "PA13/JTMS/SWDIO_34") (pintype "bidirectional"))
    )
    (net (code "28") (name "LED_1") (class "Default")
      (node (ref "R33") (pin "1") (pinfunction "1_1") (pintype "passive"))
      (node (ref "UC1") (pin "33") (pinfunction "PA12/USART1_RTS/CAN_TX/TIM1_ETR/USBDP_33") (pintype "bidirectional"))
    )
    (net (code "29") (name "LED_2") (class "Default")
      (node (ref "R36") (pin "1") (pinfunction "1_1") (pintype "passive"))
      (node (ref "UC1") (pin "32") (pinfunction "PA11/USART1_CTS/CAN_RX/TIM1_CH4/USBDM_32") (pintype "bidirectional"))
    )
    (net (code "30") (name "LED_3") (class "Default")
      (node (ref "R41") (pin "1") (pinfunction "1_1") (pintype "passive"))
      (node (ref "UC1") (pin "29") (pinfunction "PA8/USART1_CK/TIM1_CH1/MCO_29") (pintype "bidirectional"))
    )
    (net (code "31") (name "LED_4") (class "Default")
      (node (ref "R42") (pin "1") (pinfunction "1_1") (pintype "passive"))
      (node (ref "UC1") (pin "27") (pinfunction "PB14/SPI2_MISO/USART3_RTS/TIM1_CH2N_27") (pintype "input"))
    )
    (net (code "32") (name "MIDI_RX") (class "Default")
      (node (ref "OK1") (pin "6") (pinfunction "VO_6") (pintype "passive"))
      (node (ref "R37") (pin "1") (pinfunction "1_1") (pintype "passive"))
      (node (ref "UC1") (pin "31") (pinfunction "PA10/USART1_RX/TIM1_CH3_31") (pintype "bidirectional"))
    )
    (net (code "33") (name "MIDI_TX") (class "Default")
      (node (ref "R40") (pin "2") (pinfunction "2_2") (pintype "passive"))
      (node (ref "UC1") (pin "30") (pinfunction "PA9/USART1_TX/TIM1_CH2_30") (pintype "input"))
    )
    (net (code "34") (name "Net-(D1-PadA)") (class "Default")
      (node (ref "D1") (pin "A") (pinfunction "A_A") (pintype "passive"))
      (node (ref "JP2") (pin "1") (pinfunction "1_1") (pintype "passive"))
      (node (ref "JP2") (pin "2") (pinfunction "2_2") (pintype "passive"))
    )
    (net (code "35") (name "Net-(D2-PadC)") (class "Default")
      (node (ref "D2") (pin "C") (pinfunction "C_C") (pintype "passive"))
      (node (ref "JP2") (pin "10") (pinfunction "10_10") (pintype "passive"))
      (node (ref "JP2") (pin "9") (pinfunction "9_9") (pintype "passive"))
    )
    (net (code "36") (name "Net-(DISP1-A)") (class "Default")
      (node (ref "DISP1") (pin "12") (pinfunction "A_12") (pintype "passive"))
      (node (ref "R3") (pin "2") (pinfunction "2_2") (pintype "passive"))
    )
    (net (code "37") (name "Net-(DISP1-B)") (class "Default")
      (node (ref "DISP1") (pin "10") (pinfunction "B_10") (pintype "passive"))
      (node (ref "R2") (pin "2") (pinfunction "2_2") (pintype "passive"))
    )
    (net (code "38") (name "Net-(DISP1-C)") (class "Default")
      (node (ref "DISP1") (pin "9") (pinfunction "C_9") (pintype "passive"))
      (node (ref "R10") (pin "2") (pinfunction "2_2") (pintype "passive"))
    )
    (net (code "39") (name "Net-(DISP1-D)") (class "Default")
      (node (ref "DISP1") (pin "7") (pinfunction "D_7") (pintype "passive"))
      (node (ref "R11") (pin "2") (pinfunction "2_2") (pintype "passive"))
    )
    (net (code "40") (name "Net-(DISP1-E)") (class "Default")
      (node (ref "DISP1") (pin "1") (pinfunction "E_1") (pintype "passive"))
      (node (ref "R16") (pin "2") (pinfunction "2_2") (pintype "passive"))
    )
    (net (code "41") (name "Net-(DISP1-F)") (class "Default")
      (node (ref "DISP1") (pin "18") (pinfunction "F_18") (pintype "passive"))
      (node (ref "R8") (pin "2") (pinfunction "2_2") (pintype "passive"))
    )
    (net (code "42") (name "Net-(DISP1-G)") (class "Default")
      (node (ref "DISP1") (pin "17") (pinfunction "G_17") (pintype "passive"))
      (node (ref "R7") (pin "2") (pinfunction "2_2") (pintype "passive"))
    )
    (net (code "43") (name "Net-(DISP1-H)") (class "Default")
      (node (ref "DISP1") (pin "15") (pinfunction "H_15") (pintype "passive"))
      (node (ref "R6") (pin "2") (pinfunction "2_2") (pintype "passive"))
    )
    (net (code "44") (name "Net-(DISP1-J)") (class "Default")
      (node (ref "DISP1") (pin "14") (pinfunction "J_14") (pintype "passive"))
      (node (ref "R5") (pin "2") (pinfunction "2_2") (pintype "passive"))
    )
    (net (code "45") (name "Net-(DISP1-K)") (class "Default")
      (node (ref "DISP1") (pin "6") (pinfunction "K_6") (pintype "passive"))
      (node (ref "R12") (pin "2") (pinfunction "2_2") (pintype "passive"))
    )
    (net (code "46") (name "Net-(DISP1-K1)") (class "Default")
      (node (ref "DISP1") (pin "16") (pinfunction "K1_16") (pintype "passive"))
      (node (ref "Q2") (pin "C") (pinfunction "C_C") (pintype "passive"))
    )
    (net (code "47") (name "Net-(DISP1-K2)") (class "Default")
      (node (ref "DISP1") (pin "11") (pinfunction "K2_11") (pintype "passive"))
      (node (ref "Q1") (pin "C") (pinfunction "C_C") (pintype "passive"))
    )
    (net (code "48") (name "Net-(DISP1-L)") (class "Default")
      (node (ref "DISP1") (pin "5") (pinfunction "L_5") (pintype "passive"))
      (node (ref "R13") (pin "2") (pinfunction "2_2") (pintype "passive"))
    )
    (net (code "49") (name "Net-(DISP1-M)") (class "Default")
      (node (ref "DISP1") (pin "4") (pinfunction "M_4") (pintype "passive"))
      (node (ref "R14") (pin "2") (pinfunction "2_2") (pintype "passive"))
    )
    (net (code "50") (name "Net-(DISP1-N)") (class "Default")
      (node (ref "DISP1") (pin "2") (pinfunction "N_2") (pintype "passive"))
      (node (ref "R15") (pin "2") (pinfunction "2_2") (pintype "passive"))
    )
    (net (code "51") (name "Net-(DISP1-P)") (class "Default")
      (node (ref "DISP1") (pin "13") (pinfunction "P_13") (pintype "passive"))
      (node (ref "R4") (pin "2") (pinfunction "2_2") (pintype "passive"))
    )
    (net (code "52") (name "Net-(IC2A-QA)") (class "Default")
      (node (ref "IC2") (pin "15") (pinfunction "QA_15") (pintype "tri_state"))
      (node (ref "R3") (pin "1") (pinfunction "1_1") (pintype "passive"))
    )
    (net (code "53") (name "Net-(IC2A-QB)") (class "Default")
      (node (ref "IC2") (pin "1") (pinfunction "QB_1") (pintype "tri_state"))
      (node (ref "R2") (pin "1") (pinfunction "1_1") (pintype "passive"))
    )
    (net (code "54") (name "Net-(IC2A-QC)") (class "Default")
      (node (ref "IC2") (pin "2") (pinfunction "QC_2") (pintype "tri_state"))
      (node (ref "R10") (pin "1") (pinfunction "1_1") (pintype "passive"))
    )
    (net (code "55") (name "Net-(IC2A-QD)") (class "Default")
      (node (ref "IC2") (pin "3") (pinfunction "QD_3") (pintype "tri_state"))
      (node (ref "R11") (pin "1") (pinfunction "1_1") (pintype "passive"))
    )
    (net (code "56") (name "Net-(IC2A-QE)") (class "Default")
      (node (ref "IC2") (pin "4") (pinfunction "QE_4") (pintype "tri_state"))
      (node (ref "R16") (pin "1") (pinfunction "1_1") (pintype "passive"))
    )
    (net (code "57") (name "Net-(IC2A-QF)") (class "Default")
      (node (ref "IC2") (pin "5") (pinfunction "QF_5") (pintype "tri_state"))
      (node (ref "R8") (pin "1") (pinfunction "1_1") (pintype "passive"))
    )
    (net (code "58") (name "Net-(IC2A-QG)") (class "Default")
      (node (ref "IC2") (pin "6") (pinfunction "QG_6") (pintype "tri_state"))
      (node (ref "R7") (pin "1") (pinfunction "1_1") (pintype "passive"))
    )
    (net (code "59") (name "Net-(IC2A-QH)") (class "Default")
      (node (ref "IC2") (pin "7") (pinfunction "QH_7") (pintype "tri_state"))
      (node (ref "R6") (pin "1") (pinfunction "1_1") (pintype "passive"))
    )
    (net (code "60") (name "Net-(IC2A-QH*)") (class "Default")
      (node (ref "IC2") (pin "9") (pinfunction "QH*_9") (pintype "tri_state"))
      (node (ref "IC3") (pin "14") (pinfunction "SER_14") (pintype "input"))
    )
    (net (code "61") (name "Net-(IC3A-QA)") (class "Default")
      (node (ref "IC3") (pin "15") (pinfunction "QA_15") (pintype "tri_state"))
      (node (ref "R5") (pin "1") (pinfunction "1_1") (pintype "passive"))
    )
    (net (code "62") (name "Net-(IC3A-QB)") (class "Default")
      (node (ref "IC3") (pin "1") (pinfunction "QB_1") (pintype "tri_state"))
      (node (ref "R12") (pin "1") (pinfunction "1_1") (pintype "passive"))
    )
    (net (code "63") (name "Net-(IC3A-QC)") (class "Default")
      (node (ref "IC3") (pin "2") (pinfunction "QC_2") (pintype "tri_state"))
      (node (ref "R13") (pin "1") (pinfunction "1_1") (pintype "passive"))
    )
    (net (code "64") (name "Net-(IC3A-QD)") (class "Default")
      (node (ref "IC3") (pin "3") (pinfunction "QD_3") (pintype "tri_state"))
      (node (ref "R14") (pin "1") (pinfunction "1_1") (pintype "passive"))
    )
    (net (code "65") (name "Net-(IC3A-QE)") (class "Default")
      (node (ref "IC3") (pin "4") (pinfunction "QE_4") (pintype "tri_state"))
      (node (ref "R15") (pin "1") (pinfunction "1_1") (pintype "passive"))
    )
    (net (code "66") (name "Net-(IC3A-QF)") (class "Default")
      (node (ref "IC3") (pin "5") (pinfunction "QF_5") (pintype "tri_state"))
      (node (ref "R4") (pin "1") (pinfunction "1_1") (pintype "passive"))
    )
    (net (code "67") (name "Net-(IC6A--IN)") (class "Default")
      (node (ref "C14") (pin "1") (pinfunction "1_1") (pintype "passive"))
      (node (ref "IC6") (pin "2") (pinfunction "-IN_2") (pintype "input"))
      (node (ref "R18") (pin "1") (pinfunction "1_1") (pintype "passive"))
      (node (ref "R26") (pin "2") (pinfunction "2_2") (pintype "passive"))
    )
    (net (code "68") (name "Net-(IC6A-OUT)") (class "Default")
      (node (ref "C14") (pin "2") (pinfunction "2_2") (pintype "passive"))
      (node (ref "IC6") (pin "1") (pinfunction "OUT_1") (pintype "output"))
      (node (ref "R24") (pin "2") (pinfunction "2_2") (pintype "passive"))
    )
    (net (code "69") (name "Net-(IC6B--IN)") (class "Default")
      (node (ref "C21") (pin "1") (pinfunction "1_1") (pintype "passive"))
      (node (ref "IC6") (pin "6") (pinfunction "-IN_6") (pintype "input"))
      (node (ref "R19") (pin "1") (pinfunction "1_1") (pintype "passive"))
      (node (ref "R28") (pin "2") (pinfunction "2_2") (pintype "passive"))
    )
    (net (code "70") (name "Net-(IC6B-OUT)") (class "Default")
      (node (ref "C21") (pin "2") (pinfunction "2_2") (pintype "passive"))
      (node (ref "IC6") (pin "7") (pinfunction "OUT_7") (pintype "output"))
      (node (ref "R30") (pin "2") (pinfunction "2_2") (pintype "passive"))
    )
    (net (code "71") (name "Net-(IC6C--IN)") (class "Default")
      (node (ref "C22") (pin "1") (pinfunction "1_1") (pintype "passive"))
      (node (ref "IC6") (pin "9") (pinfunction "-IN_9") (pintype "input"))
      (node (ref "R20") (pin "1") (pinfunction "1_1") (pintype "passive"))
      (node (ref "R29") (pin "2") (pinfunction "2_2") (pintype "passive"))
    )
    (net (code "72") (name "Net-(IC6C-OUT)") (class "Default")
      (node (ref "C22") (pin "2") (pinfunction "2_2") (pintype "passive"))
      (node (ref "IC6") (pin "8") (pinfunction "OUT_8") (pintype "output"))
      (node (ref "R31") (pin "2") (pinfunction "2_2") (pintype "passive"))
    )
    (net (code "73") (name "Net-(IC6D--IN)") (class "Default")
      (node (ref "C16") (pin "1") (pinfunction "1_1") (pintype "passive"))
      (node (ref "IC6") (pin "13") (pinfunction "-IN_13") (pintype "input"))
      (node (ref "R21") (pin "1") (pinfunction "1_1") (pintype "passive"))
      (node (ref "R27") (pin "2") (pinfunction "2_2") (pintype "passive"))
    )
    (net (code "74") (name "Net-(IC6D-OUT)") (class "Default")
      (node (ref "C16") (pin "2") (pinfunction "2_2") (pintype "passive"))
      (node (ref "IC6") (pin "14") (pinfunction "OUT_14") (pintype "output"))
      (node (ref "R25") (pin "2") (pinfunction "2_2") (pintype "passive"))
    )
    (net (code "75") (name "Net-(IC7A-O)") (class "Default")
      (node (ref "IC7") (pin "4") (pinfunction "O_4") (pintype "tri_state"))
      (node (ref "R32") (pin "2") (pinfunction "2_2") (pintype "passive"))
    )
    (net (code "76") (name "Net-(IC8A-O)") (class "Default")
      (node (ref "IC8") (pin "4") (pinfunction "O_4") (pintype "tri_state"))
      (node (ref "R34") (pin "2") (pinfunction "2_2") (pintype "passive"))
    )
    (net (code "77") (name "Net-(IC10A-O)") (class "Default")
      (node (ref "IC10") (pin "4") (pinfunction "O_4") (pintype "tri_state"))
      (node (ref "R38") (pin "2") (pinfunction "2_2") (pintype "passive"))
    )
    (net (code "78") (name "Net-(IC11A-O)") (class "Default")
      (node (ref "IC11") (pin "4") (pinfunction "O_4") (pintype "tri_state"))
      (node (ref "R43") (pin "2") (pinfunction "2_2") (pintype "passive"))
    )
    (net (code "79") (name "Net-(J1-2)") (class "Default")
      (node (ref "J1") (pin "TIP") (pinfunction "2_TIP") (pintype "passive"))
      (node (ref "R25") (pin "1") (pinfunction "1_1") (pintype "passive"))
      (node (ref "R27") (pin "1") (pinfunction "1_1") (pintype "passive"))
    )
    (net (code "80") (name "Net-(J2-2)") (class "Default")
      (node (ref "J2") (pin "TIP") (pinfunction "2_TIP") (pintype "passive"))
      (node (ref "R32") (pin "1") (pinfunction "1_1") (pintype "passive"))
    )
    (net (code "81") (name "Net-(J3-2)") (class "Default")
      (node (ref "J3") (pin "TIP") (pinfunction "2_TIP") (pintype "passive"))
      (node (ref "R29") (pin "1") (pinfunction "1_1") (pintype "passive"))
      (node (ref "R31") (pin "1") (pinfunction "1_1") (pintype "passive"))
    )
    (net (code "82") (name "Net-(J4-2)") (class "Default")
      (node (ref "J4") (pin "TIP") (pinfunction "2_TIP") (pintype "passive"))
      (node (ref "R34") (pin "1") (pinfunction "1_1") (pintype "passive"))
    )
    (net (code "83") (name "Net-(J5-2)") (class "Default")
      (node (ref "J5") (pin "TIP") (pinfunction "2_TIP") (pintype "passive"))
      (node (ref "R28") (pin "1") (pinfunction "1_1") (pintype "passive"))
      (node (ref "R30") (pin "1") (pinfunction "1_1") (pintype "passive"))
    )
    (net (code "84") (name "Net-(J6-2)") (class "Default")
      (node (ref "J6") (pin "TIP") (pinfunction "2_TIP") (pintype "passive"))
      (node (ref "R38") (pin "1") (pinfunction "1_1") (pintype "passive"))
    )
    (net (code "85") (name "Net-(J7-2)") (class "Default")
      (node (ref "J7") (pin "TIP") (pinfunction "2_TIP") (pintype "passive"))
      (node (ref "R24") (pin "1") (pinfunction "1_1") (pintype "passive"))
      (node (ref "R26") (pin "1") (pinfunction "1_1") (pintype "passive"))
    )
    (net (code "86") (name "Net-(J8-2)") (class "Default")
      (node (ref "J8") (pin "TIP") (pinfunction "2_TIP") (pintype "passive"))
      (node (ref "R43") (pin "1") (pinfunction "1_1") (pintype "passive"))
    )
    (net (code "87") (name "Net-(LED1-PadA)") (class "Default")
      (node (ref "LED1") (pin "A") (pinfunction "A_A") (pintype "passive"))
      (node (ref "R33") (pin "2") (pinfunction "2_2") (pintype "passive"))
    )
    (net (code "88") (name "Net-(LED2-PadA)") (class "Default")
      (node (ref "LED2") (pin "A") (pinfunction "A_A") (pintype "passive"))
      (node (ref "R36") (pin "2") (pinfunction "2_2") (pintype "passive"))
    )
    (net (code "89") (name "Net-(LED3-PadA)") (class "Default")
      (node (ref "LED3") (pin "A") (pinfunction "A_A") (pintype "passive"))
      (node (ref "R41") (pin "2") (pinfunction "2_2") (pintype "passive"))
    )
    (net (code "90") (name "Net-(LED4-PadA)") (class "Default")
      (node (ref "LED4") (pin "A") (pinfunction "A_A") (pintype "passive"))
      (node (ref "R42") (pin "2") (pinfunction "2_2") (pintype "passive"))
    )
    (net (code "91") (name "Net-(OK1-A)") (class "Default")
      (node (ref "D3") (pin "C") (pinfunction "C_C") (pintype "passive"))
      (node (ref "OK1") (pin "2") (pinfunction "A_2") (pintype "passive"))
      (node (ref "R35") (pin "1") (pinfunction "1_1") (pintype "passive"))
    )
    (net (code "92") (name "Net-(OK1-C)") (class "Default")
      (node (ref "D3") (pin "A") (pinfunction "A_A") (pintype "passive"))
      (node (ref "OK1") (pin "3") (pinfunction "C_3") (pintype "passive"))
      (node (ref "X1") (pin "5") (pinfunction "5_5") (pintype "passive"))
    )
    (net (code "93") (name "Net-(Q1-PadB)") (class "Default")
      (node (ref "Q1") (pin "B") (pinfunction "B_B") (pintype "passive"))
      (node (ref "R1") (pin "2") (pinfunction "2_2") (pintype "passive"))
    )
    (net (code "94") (name "Net-(Q2-PadB)") (class "Default")
      (node (ref "Q2") (pin "B") (pinfunction "B_B") (pintype "passive"))
      (node (ref "R9") (pin "2") (pinfunction "2_2") (pintype "passive"))
    )
    (net (code "95") (name "Net-(R35-Pad2)") (class "Default")
      (node (ref "R35") (pin "2") (pinfunction "2_2") (pintype "passive"))
      (node (ref "X1") (pin "4") (pinfunction "4_4") (pintype "passive"))
    )
    (net (code "96") (name "Net-(R39-Pad1)") (class "Default")
      (node (ref "R39") (pin "1") (pinfunction "1_1") (pintype "passive"))
      (node (ref "X2") (pin "4") (pinfunction "4_4") (pintype "passive"))
    )
    (net (code "97") (name "Net-(R40-Pad1)") (class "Default")
      (node (ref "R40") (pin "1") (pinfunction "1_1") (pintype "passive"))
      (node (ref "X2") (pin "5") (pinfunction "5_5") (pintype "passive"))
    )
    (net (code "98") (name "Net-(UC1-PD0-OSC_IN)") (class "Default")
      (node (ref "C7") (pin "2") (pinfunction "2_2") (pintype "passive"))
      (node (ref "Q3") (pin "2") (pinfunction "2_2") (pintype "passive"))
      (node (ref "UC1") (pin "5") (pinfunction "PD0-OSC_IN_5") (pintype "input"))
    )
    (net (code "99") (name "Net-(UC1-PD1-OSC_OUT)") (class "Default")
      (node (ref "C10") (pin "2") (pinfunction "2_2") (pintype "passive"))
      (node (ref "Q3") (pin "1") (pinfunction "1_1") (pintype "passive"))
      (node (ref "UC1") (pin "6") (pinfunction "PD1-OSC_OUT_6") (pintype "input"))
    )
    (net (code "100") (name "RESET") (class "Default")
      (node (ref "JP4") (pin "10") (pinfunction "10_10") (pintype "passive"))
      (node (ref "R17") (pin "1") (pinfunction "1_1") (pintype "passive"))
      (node (ref "UC1") (pin "7") (pinfunction "NRST_7") (pintype "input"))
    )
    (net (code "101") (name "SWITCH_0") (class "Default")
      (node (ref "SW2") (pin "A1") (pinfunction "S_A1") (pintype "passive"))
      (node (ref "SW2") (pin "A2") (pinfunction "S1_A2") (pintype "passive"))
      (node (ref "UC1") (pin "15") (pinfunction "PA5/SPI1_SCK/ADC12_IN5_15") (pintype "bidirectional"))
    )
    (net (code "102") (name "SWITCH_1") (class "Default")
      (node (ref "SW3") (pin "A1") (pinfunction "S_A1") (pintype "passive"))
      (node (ref "SW3") (pin "A2") (pinfunction "S1_A2") (pintype "passive"))
      (node (ref "UC1") (pin "16") (pinfunction "PA6/SPI1_MISO/ADC12_IN6/TIM3_CH1_16") (pintype "bidirectional"))
    )
    (net (code "103") (name "SWITCH_2") (class "Default")
      (node (ref "SW4") (pin "A1") (pinfunction "S_A1") (pintype "passive"))
      (node (ref "SW4") (pin "A2") (pinfunction "S1_A2") (pintype "passive"))
      (node (ref "UC1") (pin "14") (pinfunction "PA4/SPI1_NSS/USART2_CK/ADC12_IN4_14") (pintype "bidirectional"))
    )
    (net (code "104") (name "VCC") (class "Default")
      (node (ref "C1") (pin "+") (pinfunction "+_+") (pintype "passive"))
      (node (ref "C12") (pin "+") (pinfunction "+_+") (pintype "passive"))
      (node (ref "C19") (pin "1") (pinfunction "1_1") (pintype "passive"))
      (node (ref "C25") (pin "1") (pinfunction "1_1") (pintype "passive"))
      (node (ref "D1") (pin "C") (pinfunction "C_C") (pintype "passive"))
      (node (ref "IC1") (pin "3") (pinfunction "VIN_3") (pintype "input"))
      (node (ref "IC5") (pin "2") (pinfunction "V+_2") (pintype "power_in"))
      (node (ref "IC6") (pin "4") (pinfunction "V+_4") (pintype "power_in"))
      (node (ref "IC9") (pin "3") (pinfunction "VI_3") (pintype "input"))
    )
    (net (code "105") (name "VEE") (class "Default")
      (node (ref "C20") (pin "2") (pinfunction "2_2") (pintype "passive"))
      (node (ref "C3") (pin "-") (pinfunction "-_-") (pintype "passive"))
      (node (ref "D2") (pin "A") (pinfunction "A_A") (pintype "passive"))
      (node (ref "IC6") (pin "11") (pinfunction "V-_11") (pintype "power_in"))
    )
    (net (code "106") (name "VREF") (class "Default")
      (node (ref "C17") (pin "1") (pinfunction "1_1") (pintype "passive"))
      (node (ref "IC4") (pin "3") (pinfunction "VREFH_3") (pintype "bidirectional"))
      (node (ref "R23") (pin "2") (pinfunction "2_2") (pintype "passive"))
    )
    (net (code "107") (name "VREF{slash}2") (class "Default")
      (node (ref "IC6") (pin "10") (pinfunction "+IN_10") (pintype "input"))
      (node (ref "IC6") (pin "12") (pinfunction "+IN_12") (pintype "input"))
      (node (ref "IC6") (pin "3") (pinfunction "+IN_3") (pintype "input"))
      (node (ref "IC6") (pin "5") (pinfunction "+IN_5") (pintype "input"))
      (node (ref "R22") (pin "2") (pinfunction "2_2") (pintype "passive"))
      (node (ref "R23") (pin "1") (pinfunction "1_1") (pintype "passive"))
    )
    (net (code "108") (name "unconnected-(DISP1-DP-Pad8)") (class "Default")
      (node (ref "DISP1") (pin "8") (pinfunction "DP_8") (pintype "passive"))
    )
    (net (code "109") (name "unconnected-(IC3A-QG-Pad6)") (class "Default")
      (node (ref "IC3") (pin "6") (pinfunction "QG_6") (pintype "tri_state"))
    )
    (net (code "110") (name "unconnected-(IC3A-QH*-Pad9)") (class "Default")
      (node (ref "IC3") (pin "9") (pinfunction "QH*_9") (pintype "tri_state"))
    )
    (net (code "111") (name "unconnected-(IC3A-QH-Pad7)") (class "Default")
      (node (ref "IC3") (pin "7") (pinfunction "QH_7") (pintype "tri_state"))
    )
    (net (code "112") (name "unconnected-(IC5-OPT-Pad3)") (class "Default")
      (node (ref "IC5") (pin "3") (pinfunction "OPT_3") (pintype "output"))
    )
    (net (code "113") (name "unconnected-(IC5-TRM-Pad5)") (class "Default")
      (node (ref "IC5") (pin "5") (pinfunction "TRM_5") (pintype "input"))
    )
    (net (code "114") (name "unconnected-(J1-3-PadSW)") (class "Default")
      (node (ref "J1") (pin "SW") (pinfunction "3_SW") (pintype "passive"))
    )
    (net (code "115") (name "unconnected-(J2-3-PadSW)") (class "Default")
      (node (ref "J2") (pin "SW") (pinfunction "3_SW") (pintype "passive"))
    )
    (net (code "116") (name "unconnected-(J3-3-PadSW)") (class "Default")
      (node (ref "J3") (pin "SW") (pinfunction "3_SW") (pintype "passive"))
    )
    (net (code "117") (name "unconnected-(J4-3-PadSW)") (class "Default")
      (node (ref "J4") (pin "SW") (pinfunction "3_SW") (pintype "passive"))
    )
    (net (code "118") (name "unconnected-(J5-3-PadSW)") (class "Default")
      (node (ref "J5") (pin "SW") (pinfunction "3_SW") (pintype "passive"))
    )
    (net (code "119") (name "unconnected-(J6-3-PadSW)") (class "Default")
      (node (ref "J6") (pin "SW") (pinfunction "3_SW") (pintype "passive"))
    )
    (net (code "120") (name "unconnected-(J7-3-PadSW)") (class "Default")
      (node (ref "J7") (pin "SW") (pinfunction "3_SW") (pintype "passive"))
    )
    (net (code "121") (name "unconnected-(J8-3-PadSW)") (class "Default")
      (node (ref "J8") (pin "SW") (pinfunction "3_SW") (pintype "passive"))
    )
    (net (code "122") (name "unconnected-(JP4-Pad7)") (class "Default")
      (node (ref "JP4") (pin "7") (pinfunction "7_7") (pintype "passive"))
    )
    (net (code "123") (name "unconnected-(OK1-VE-Pad7)") (class "Default")
      (node (ref "OK1") (pin "7") (pinfunction "VE_7") (pintype "passive"))
    )
    (net (code "124") (name "unconnected-(UC1-PA0_WKUP{slash}USART2_CTS{slash}ADC12_IN0{slash}TIM2_CH1_ETR-Pad10)") (class "Default")
      (node (ref "UC1") (pin "10") (pinfunction "PA0_WKUP/USART2_CTS/ADC12_IN0/TIM2_CH1_ETR_10") (pintype "bidirectional"))
    )
    (net (code "125") (name "unconnected-(UC1-PA1{slash}USART2_RTS{slash}ADC12_IN1{slash}TIM2_CH2-Pad11)") (class "Default")
      (node (ref "UC1") (pin "11") (pinfunction "PA1/USART2_RTS/ADC12_IN1/TIM2_CH2_11") (pintype "bidirectional"))
    )
    (net (code "126") (name "unconnected-(UC1-PA2{slash}USART2_TX{slash}ADC12_IN2{slash}TIM2_CH3-Pad12)") (class "Default")
      (node (ref "UC1") (pin "12") (pinfunction "PA2/USART2_TX/ADC12_IN2/TIM2_CH3_12") (pintype "bidirectional"))
    )
    (net (code "127") (name "unconnected-(UC1-PA3{slash}USART2_RX{slash}ADC12_IN3{slash}TIM2_CH4-Pad13)") (class "Default")
      (node (ref "UC1") (pin "13") (pinfunction "PA3/USART2_RX/ADC12_IN3/TIM2_CH4_13") (pintype "bidirectional"))
    )
    (net (code "128") (name "unconnected-(UC1-PA7{slash}SPI1_MOSI{slash}ADC12_IN7{slash}TIM3_CH2-Pad17)") (class "Default")
      (node (ref "UC1") (pin "17") (pinfunction "PA7/SPI1_MOSI/ADC12_IN7/TIM3_CH2_17") (pintype "bidirectional"))
    )
    (net (code "129") (name "unconnected-(UC1-PB4{slash}NJTRST-Pad40)") (class "Default")
      (node (ref "UC1") (pin "40") (pinfunction "PB4/NJTRST_40") (pintype "bidirectional"))
    )
    (net (code "130") (name "unconnected-(X1-Pad1)") (class "Default")
      (node (ref "X1") (pin "1") (pinfunction "1_1") (pintype "passive"))
    )
    (net (code "131") (name "unconnected-(X1-Pad2)") (class "Default")
      (node (ref "X1") (pin "2") (pinfunction "2_2") (pintype "passive"))
    )
    (net (code "132") (name "unconnected-(X1-Pad3)") (class "Default")
      (node (ref "X1") (pin "3") (pinfunction "3_3") (pintype "passive"))
    )
    (net (code "133") (name "unconnected-(X2-Pad1)") (class "Default")
      (node (ref "X2") (pin "1") (pinfunction "1_1") (pintype "passive"))
    )
    (net (code "134") (name "unconnected-(X2-Pad3)") (class "Default")
      (node (ref "X2") (pin "3") (pinfunction "3_3") (pintype "passive"))
    )
  )
)
